# Sheet1.net
KiCad netlist of a schematic drawn in Altium Designer
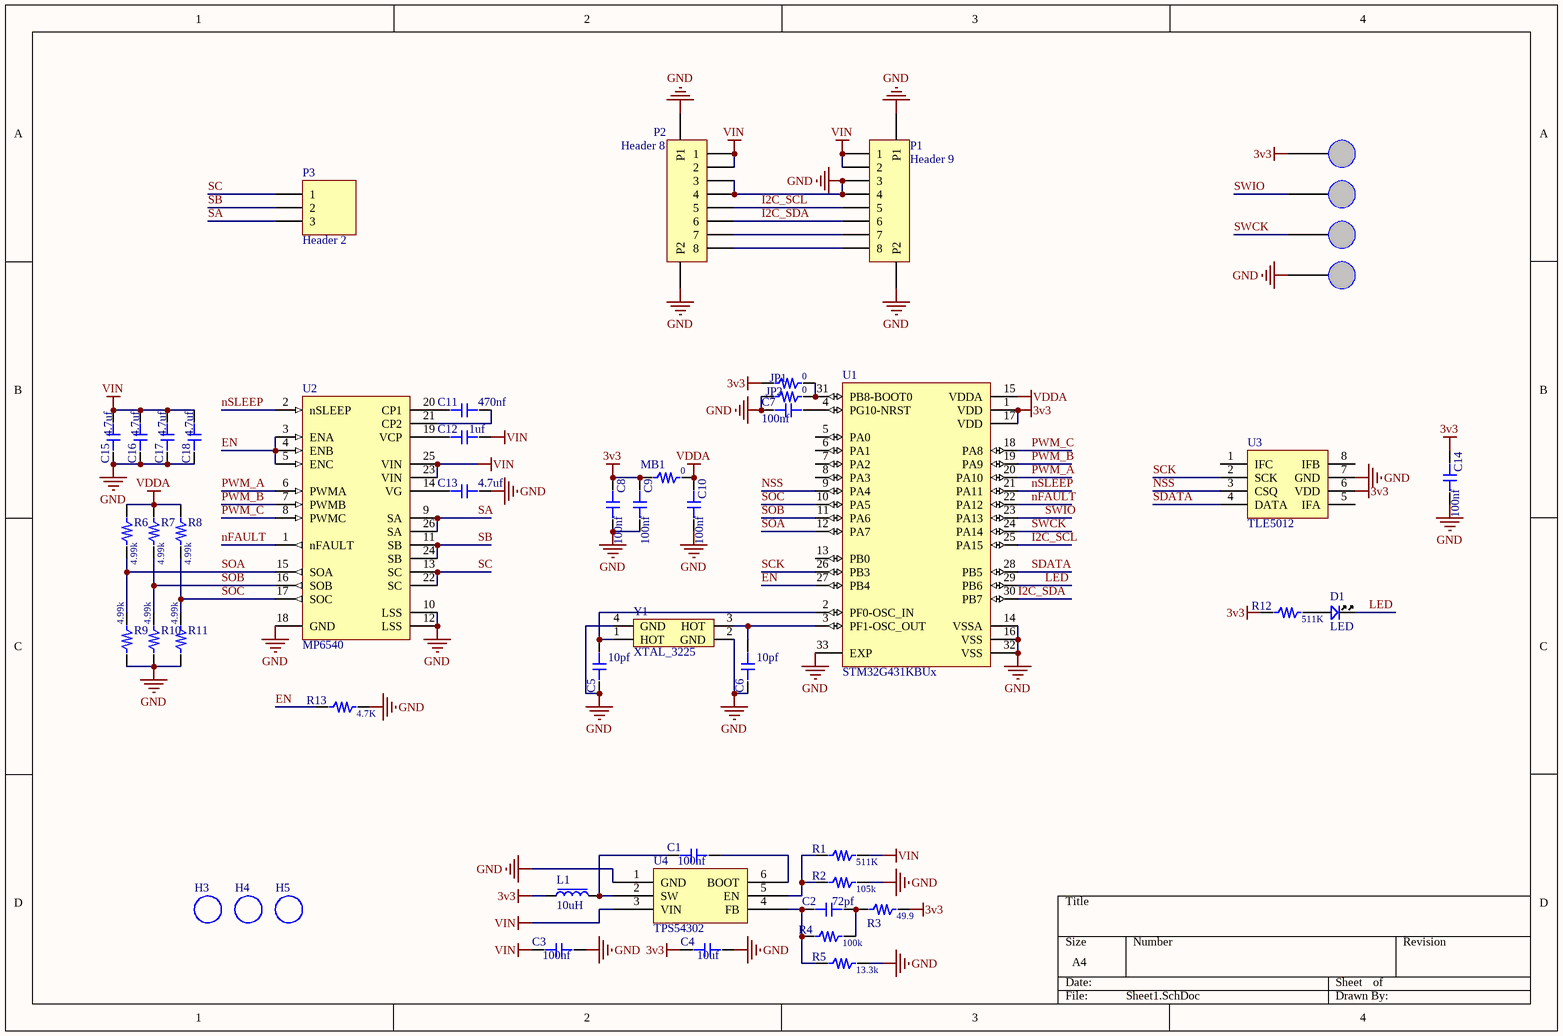
[diagram p0: Sheet1.SchDoc]

(export (version "E")
  (design (tool "Eeschema 10.0.6"))
  (components
    (comp (ref "3V3")
      (value "solder_pad")
      (footprint "solder_pad_1")
      (libsource (lib "zjti_lib") (part "solder_pad"))
    )
    (comp (ref "C1")
      (value "100nf")
      (footprint "C_0402")
      (fields (field (name "Comment") "C_0603"))
      (libsource (lib "zjti_lib") (part "C"))
    )
    (comp (ref "C2")
      (value "72pf")
      (footprint "C_0402")
      (fields (field (name "Comment") "C_0603"))
      (libsource (lib "zjti_lib") (part "C"))
    )
    (comp (ref "C3")
      (value "100nf")
      (footprint "C_0402")
      (fields (field (name "Comment") "C_0603"))
      (libsource (lib "zjti_lib") (part "C"))
    )
    (comp (ref "C4")
      (value "10uf")
      (footprint "C_0603")
      (fields (field (name "Comment") "C_0603"))
      (libsource (lib "zjti_lib") (part "C"))
    )
    (comp (ref "C5")
      (value "10pf")
      (footprint "C_0402")
      (fields (field (name "Comment") "C_0603"))
      (libsource (lib "zjti_lib") (part "C"))
    )
    (comp (ref "C6")
      (value "10pf")
      (footprint "C_0402")
      (fields (field (name "Comment") "C_0603"))
      (libsource (lib "zjti_lib") (part "C"))
    )
    (comp (ref "C7")
      (value "100nf")
      (footprint "C_0402")
      (fields (field (name "Comment") "C_0603"))
      (libsource (lib "zjti_lib") (part "C"))
    )
    (comp (ref "C8")
      (value "100nf")
      (footprint "C_0402")
      (fields (field (name "Comment") "C_0603"))
      (libsource (lib "zjti_lib") (part "C"))
    )
    (comp (ref "C9")
      (value "100nf")
      (footprint "C_0402")
      (fields (field (name "Comment") "C_0603"))
      (libsource (lib "zjti_lib") (part "C"))
    )
    (comp (ref "C10")
      (value "100nf")
      (footprint "C_0402")
      (fields (field (name "Comment") "C_0603"))
      (libsource (lib "zjti_lib") (part "C"))
    )
    (comp (ref "C11")
      (value "470nf")
      (footprint "C_0402")
      (fields (field (name "Comment") "C_0603"))
      (libsource (lib "zjti_lib") (part "C"))
    )
    (comp (ref "C12")
      (value "1uf")
      (footprint "C_0402")
      (fields (field (name "Comment") "C_0603"))
      (libsource (lib "zjti_lib") (part "C"))
    )
    (comp (ref "C13")
      (value "4.7uf")
      (footprint "C_0402")
      (fields (field (name "Comment") "C_0603"))
      (libsource (lib "zjti_lib") (part "C"))
    )
    (comp (ref "C14")
      (value "100nf")
      (footprint "C_0402")
      (fields (field (name "Comment") "C_0603"))
      (libsource (lib "zjti_lib") (part "C"))
    )
    (comp (ref "C15")
      (value "4.7uf")
      (footprint "C_0805")
      (fields (field (name "Comment") "C_0603"))
      (libsource (lib "zjti_lib") (part "C"))
    )
    (comp (ref "C16")
      (value "4.7uf")
      (footprint "C_0805")
      (fields (field (name "Comment") "C_0603"))
      (libsource (lib "zjti_lib") (part "C"))
    )
    (comp (ref "C17")
      (value "4.7uf")
      (footprint "C_0805")
      (fields (field (name "Comment") "C_0603"))
      (libsource (lib "zjti_lib") (part "C"))
    )
    (comp (ref "C18")
      (value "4.7uf")
      (footprint "C_0805")
      (fields (field (name "Comment") "C_0603"))
      (libsource (lib "zjti_lib") (part "C"))
    )
    (comp (ref "CK")
      (value "solder_pad")
      (footprint "solder_pad_1")
      (libsource (lib "zjti_lib") (part "solder_pad"))
    )
    (comp (ref "D1") (value "LED") (footprint "LED_0603") (libsource (lib "zjti_lib") (part "LED_SMD")))
    (comp (ref "GND")
      (value "solder_pad")
      (footprint "solder_pad_1")
      (libsource (lib "zjti_lib") (part "solder_pad"))
    )
    (comp (ref "H3")
      (value "~")
      (footprint "M3 Hole")
      (description "M3 Hole with no copper")
      (libsource (lib "CustomComponents") (part "M3 Hole"))
    )
    (comp (ref "H4")
      (value "~")
      (footprint "M3 Hole")
      (description "M3 Hole with no copper")
      (libsource (lib "CustomComponents") (part "M3 Hole"))
    )
    (comp (ref "H5")
      (value "~")
      (footprint "M3 Hole")
      (description "M3 Hole with no copper")
      (libsource (lib "CustomComponents") (part "M3 Hole"))
    )
    (comp (ref "IO")
      (value "solder_pad")
      (footprint "solder_pad_1")
      (libsource (lib "zjti_lib") (part "solder_pad"))
    )
    (comp (ref "JP1")
      (value "0")
      (footprint "R_0402")
      (fields (field (name "Comment") "R_0603"))
      (libsource (lib "zjti_lib") (part "R"))
    )
    (comp (ref "JP2")
      (value "0")
      (footprint "R_0402")
      (fields (field (name "Comment") "R_0603"))
      (libsource (lib "zjti_lib") (part "R"))
    )
    (comp (ref "L1")
      (value "10uH")
      (footprint "NR3015")
      (description "NR功率电感")
      (libsource (lib "zjti_lib") (part "L-NR"))
    )
    (comp (ref "MB1")
      (value "0")
      (footprint "R_0402")
      (fields (field (name "Comment") "R_0603"))
      (libsource (lib "zjti_lib") (part "R"))
    )
    (comp (ref "P1")
      (value "Header 9")
      (footprint "JST_SM08B-SRSS-TB(LF)(SN)")
      (description "Header, 5-Pin")
      (fields (field (name "PUBLISHER") "Altium Limited"))
      (libsource (lib "") (part "Header 8_1"))
    )
    (comp (ref "P2")
      (value "Header 8")
      (footprint "JST_SM08B-SRSS-TB(LF)(SN)")
      (description "Header, 5-Pin")
      (fields (field (name "PUBLISHER") "Altium Limited"))
      (libsource (lib "zjti_lib") (part "Header 8"))
    )
    (comp (ref "P3")
      (value "Header 2")
      (footprint "MOLEX_530480310")
      (description "Header, 2-Pin")
      (fields (field (name "PUBLISHER") "Altium Limited"))
      (libsource (lib "zjti_lib") (part "Header 3"))
    )
    (comp (ref "R1")
      (value "511K")
      (footprint "R_0402")
      (fields (field (name "Comment") "R_0603"))
      (libsource (lib "zjti_lib") (part "R"))
    )
    (comp (ref "R2")
      (value "105k")
      (footprint "R_0402")
      (fields (field (name "Comment") "R_0603"))
      (libsource (lib "zjti_lib") (part "R"))
    )
    (comp (ref "R3")
      (value "49.9")
      (footprint "R_0402")
      (fields (field (name "Comment") "R_0603"))
      (libsource (lib "zjti_lib") (part "R"))
    )
    (comp (ref "R4")
      (value "100k")
      (footprint "R_0402")
      (fields (field (name "Comment") "R_0603"))
      (libsource (lib "zjti_lib") (part "R"))
    )
    (comp (ref "R5")
      (value "13.3k")
      (footprint "R_0402")
      (fields (field (name "Comment") "R_0603"))
      (libsource (lib "zjti_lib") (part "R"))
    )
    (comp (ref "R6")
      (value "4.99k")
      (footprint "R_0402")
      (fields (field (name "Comment") "R_0603"))
      (libsource (lib "zjti_lib") (part "R"))
    )
    (comp (ref "R7")
      (value "4.99k")
      (footprint "R_0402")
      (fields (field (name "Comment") "R_0603"))
      (libsource (lib "zjti_lib") (part "R"))
    )
    (comp (ref "R8")
      (value "4.99k")
      (footprint "R_0402")
      (fields (field (name "Comment") "R_0603"))
      (libsource (lib "zjti_lib") (part "R"))
    )
    (comp (ref "R9")
      (value "4.99k")
      (footprint "R_0402")
      (fields (field (name "Comment") "R_0603"))
      (libsource (lib "zjti_lib") (part "R"))
    )
    (comp (ref "R10")
      (value "4.99k")
      (footprint "R_0402")
      (fields (field (name "Comment") "R_0603"))
      (libsource (lib "zjti_lib") (part "R"))
    )
    (comp (ref "R11")
      (value "4.99k")
      (footprint "R_0402")
      (fields (field (name "Comment") "R_0603"))
      (libsource (lib "zjti_lib") (part "R"))
    )
    (comp (ref "R12")
      (value "511K")
      (footprint "R_0402")
      (fields (field (name "Comment") "R_0603"))
      (libsource (lib "zjti_lib") (part "R"))
    )
    (comp (ref "R13")
      (value "4.7K")
      (footprint "R_0402")
      (fields (field (name "Comment") "R_0603"))
      (libsource (lib "zjti_lib") (part "R"))
    )
    (comp (ref "U1")
      (value "STM32G431KBUx")
      (footprint "QFN32")
      (description "ARMÂ® CortexÂ®-M4F STM32G4 Microcontroller IC 32-Bit 170MHz 128KB (128K x 8) FLASH 32-UFQFPN (5x5)")
      (fields (field (name "MP") "STM32G431KBU3") (field (name "MF") "STMicroelectronics"))
      (libsource (lib "zjti_lib") (part "STM32G431KBUx"))
    )
    (comp (ref "U2")
      (value "MP6540")
      (footprint "QFN26-MPS")
      (fields (field (name "MP") "STM32G431KBU3") (field (name "MF") "STMicroelectronics"))
      (libsource (lib "zjti_lib") (part "MP6540"))
    )
    (comp (ref "U3") (value "TLE5012") (footprint "SOIC8") (libsource (lib "zjti_lib") (part "TLE5012")))
    (comp (ref "U4") (value "TPS54302") (footprint "SOT-23-6") (libsource (lib "zjti_lib") (part "TPS54302")))
    (comp (ref "Y1")
      (value "XTAL_3225")
      (footprint "XTAL-2016")
      (libsource (lib "zjti_lib") (part "XTAL_3225"))
    )
  )
  (nets
    (net (code "1") (name "/EN") (class "Default")
      (node (ref "R13") (pin "1") (pinfunction "1_1") (pintype "passive"))
      (node (ref "U1") (pin "27") (pinfunction "PB4_27") (pintype "bidirectional"))
      (node (ref "U2") (pin "3") (pinfunction "ENA_3") (pintype "input"))
      (node (ref "U2") (pin "4") (pinfunction "ENB_4") (pintype "input"))
      (node (ref "U2") (pin "5") (pinfunction "ENC_5") (pintype "input"))
    )
    (net (code "2") (name "/I2C_SCL") (class "Default")
      (node (ref "P1") (pin "5") (pinfunction "5_5") (pintype "passive"))
      (node (ref "P2") (pin "5") (pinfunction "5_5") (pintype "passive"))
      (node (ref "U1") (pin "25") (pinfunction "PA15_25") (pintype "bidirectional"))
    )
    (net (code "3") (name "/I2C_SDA") (class "Default")
      (node (ref "P1") (pin "6") (pinfunction "6_6") (pintype "passive"))
      (node (ref "P2") (pin "6") (pinfunction "6_6") (pintype "passive"))
      (node (ref "U1") (pin "30") (pinfunction "PB7_30") (pintype "bidirectional"))
    )
    (net (code "4") (name "/LED") (class "Default")
      (node (ref "D1") (pin "C") (pintype "passive"))
      (node (ref "U1") (pin "29") (pinfunction "PB6_29") (pintype "bidirectional"))
    )
    (net (code "5") (name "/NSS") (class "Default")
      (node (ref "U1") (pin "9") (pinfunction "PA4_9") (pintype "bidirectional"))
      (node (ref "U3") (pin "3") (pinfunction "CSQ_3") (pintype "passive"))
    )
    (net (code "6") (name "/PWM_A") (class "Default")
      (node (ref "U1") (pin "20") (pinfunction "PA10_20") (pintype "bidirectional"))
      (node (ref "U2") (pin "6") (pinfunction "PWMA_6") (pintype "input"))
    )
    (net (code "7") (name "/PWM_B") (class "Default")
      (node (ref "U1") (pin "19") (pinfunction "PA9_19") (pintype "bidirectional"))
      (node (ref "U2") (pin "7") (pinfunction "PWMB_7") (pintype "input"))
    )
    (net (code "8") (name "/PWM_C") (class "Default")
      (node (ref "U1") (pin "18") (pinfunction "PA8_18") (pintype "bidirectional"))
      (node (ref "U2") (pin "8") (pinfunction "PWMC_8") (pintype "input"))
    )
    (net (code "9") (name "/SA") (class "Default")
      (node (ref "P3") (pin "3") (pinfunction "3_3") (pintype "passive"))
      (node (ref "U2") (pin "26") (pinfunction "SA_26") (pintype "power_in"))
      (node (ref "U2") (pin "9") (pinfunction "SA_9") (pintype "power_in"))
    )
    (net (code "10") (name "/SB") (class "Default")
      (node (ref "P3") (pin "2") (pinfunction "2_2") (pintype "passive"))
      (node (ref "U2") (pin "11") (pinfunction "SB_11") (pintype "power_in"))
      (node (ref "U2") (pin "24") (pinfunction "SB_24") (pintype "power_in"))
    )
    (net (code "11") (name "/SC") (class "Default")
      (node (ref "P3") (pin "1") (pinfunction "1_1") (pintype "passive"))
      (node (ref "U2") (pin "13") (pinfunction "SC_13") (pintype "power_in"))
      (node (ref "U2") (pin "22") (pinfunction "SC_22") (pintype "power_in"))
    )
    (net (code "12") (name "/SCK") (class "Default")
      (node (ref "U1") (pin "26") (pinfunction "PB3_26") (pintype "bidirectional"))
      (node (ref "U3") (pin "2") (pinfunction "SCK_2") (pintype "passive"))
    )
    (net (code "13") (name "/SDATA") (class "Default")
      (node (ref "U1") (pin "28") (pinfunction "PB5_28") (pintype "bidirectional"))
      (node (ref "U3") (pin "4") (pinfunction "DATA_4") (pintype "passive"))
    )
    (net (code "14") (name "/SOA") (class "Default")
      (node (ref "R6") (pin "1") (pinfunction "1_1") (pintype "passive"))
      (node (ref "R9") (pin "2") (pinfunction "2_2") (pintype "passive"))
      (node (ref "U1") (pin "12") (pinfunction "PA7_12") (pintype "bidirectional"))
      (node (ref "U2") (pin "15") (pinfunction "SOA_15") (pintype "output"))
    )
    (net (code "15") (name "/SOB") (class "Default")
      (node (ref "R10") (pin "2") (pinfunction "2_2") (pintype "passive"))
      (node (ref "R7") (pin "1") (pinfunction "1_1") (pintype "passive"))
      (node (ref "U1") (pin "11") (pinfunction "PA6_11") (pintype "bidirectional"))
      (node (ref "U2") (pin "16") (pinfunction "SOB_16") (pintype "output"))
    )
    (net (code "16") (name "/SOC") (class "Default")
      (node (ref "R11") (pin "2") (pinfunction "2_2") (pintype "passive"))
      (node (ref "R8") (pin "1") (pinfunction "1_1") (pintype "passive"))
      (node (ref "U1") (pin "10") (pinfunction "PA5_10") (pintype "bidirectional"))
      (node (ref "U2") (pin "17") (pinfunction "SOC_17") (pintype "output"))
    )
    (net (code "17") (name "/SWCK") (class "Default")
      (node (ref "CK") (pin "1") (pinfunction "1_1") (pintype "passive"))
      (node (ref "U1") (pin "24") (pinfunction "PA14_24") (pintype "bidirectional"))
    )
    (net (code "18") (name "/SWIO") (class "Default")
      (node (ref "IO") (pin "1") (pinfunction "1_1") (pintype "passive"))
      (node (ref "U1") (pin "23") (pinfunction "PA13_23") (pintype "bidirectional"))
    )
    (net (code "19") (name "/nFAULT") (class "Default")
      (node (ref "U1") (pin "22") (pinfunction "PA12_22") (pintype "bidirectional"))
      (node (ref "U2") (pin "1") (pinfunction "nFAULT_1") (pintype "output"))
    )
    (net (code "20") (name "/nSLEEP") (class "Default")
      (node (ref "U1") (pin "21") (pinfunction "PA11_21") (pintype "bidirectional"))
      (node (ref "U2") (pin "2") (pinfunction "nSLEEP_2") (pintype "input"))
    )
    (net (code "21") (name "3v3") (class "Default")
      (node (ref "3V3") (pin "1") (pinfunction "1_1") (pintype "passive"))
      (node (ref "C14") (pin "1") (pinfunction "1_1") (pintype "passive"))
      (node (ref "C4") (pin "1") (pinfunction "1_1") (pintype "passive"))
      (node (ref "C8") (pin "1") (pinfunction "1_1") (pintype "passive"))
      (node (ref "C9") (pin "1") (pinfunction "1_1") (pintype "passive"))
      (node (ref "JP1") (pin "1") (pinfunction "1_1") (pintype "passive"))
      (node (ref "L1") (pin "1") (pinfunction "1_1") (pintype "passive"))
      (node (ref "MB1") (pin "1") (pinfunction "1_1") (pintype "passive"))
      (node (ref "R12") (pin "1") (pinfunction "1_1") (pintype "passive"))
      (node (ref "R3") (pin "2") (pinfunction "2_2") (pintype "passive"))
      (node (ref "U1") (pin "1") (pinfunction "VDD_1") (pintype "power_in"))
      (node (ref "U1") (pin "17") (pinfunction "VDD_17") (pintype "power_in"))
      (node (ref "U3") (pin "6") (pinfunction "VDD_6") (pintype "passive"))
    )
    (net (code "22") (name "GND") (class "Default")
      (node (ref "C10") (pin "2") (pinfunction "2_2") (pintype "passive"))
      (node (ref "C13") (pin "2") (pinfunction "2_2") (pintype "passive"))
      (node (ref "C14") (pin "2") (pinfunction "2_2") (pintype "passive"))
      (node (ref "C15") (pin "1") (pinfunction "1_1") (pintype "passive"))
      (node (ref "C16") (pin "1") (pinfunction "1_1") (pintype "passive"))
      (node (ref "C17") (pin "1") (pinfunction "1_1") (pintype "passive"))
      (node (ref "C18") (pin "1") (pinfunction "1_1") (pintype "passive"))
      (node (ref "C3") (pin "2") (pinfunction "2_2") (pintype "passive"))
      (node (ref "C4") (pin "2") (pinfunction "2_2") (pintype "passive"))
      (node (ref "C5") (pin "1") (pinfunction "1_1") (pintype "passive"))
      (node (ref "C6") (pin "1") (pinfunction "1_1") (pintype "passive"))
      (node (ref "C7") (pin "1") (pinfunction "1_1") (pintype "passive"))
      (node (ref "C8") (pin "2") (pinfunction "2_2") (pintype "passive"))
      (node (ref "C9") (pin "2") (pinfunction "2_2") (pintype "passive"))
      (node (ref "GND") (pin "1") (pinfunction "1_1") (pintype "passive"))
      (node (ref "JP2") (pin "1") (pinfunction "1_1") (pintype "passive"))
      (node (ref "P1") (pin "3") (pinfunction "3_3") (pintype "passive"))
      (node (ref "P1") (pin "4") (pinfunction "4_4") (pintype "passive"))
      (node (ref "P1") (pin "P1") (pinfunction "P1_P1") (pintype "passive"))
      (node (ref "P1") (pin "P2") (pinfunction "P2_P2") (pintype "passive"))
      (node (ref "P2") (pin "3") (pinfunction "3_3") (pintype "passive"))
      (node (ref "P2") (pin "4") (pinfunction "4_4") (pintype "passive"))
      (node (ref "P2") (pin "P1") (pinfunction "P1_P1") (pintype "passive"))
      (node (ref "P2") (pin "P2") (pinfunction "P2_P2") (pintype "passive"))
      (node (ref "R10") (pin "1") (pinfunction "1_1") (pintype "passive"))
      (node (ref "R11") (pin "1") (pinfunction "1_1") (pintype "passive"))
      (node (ref "R13") (pin "2") (pinfunction "2_2") (pintype "passive"))
      (node (ref "R2") (pin "2") (pinfunction "2_2") (pintype "passive"))
      (node (ref "R5") (pin "2") (pinfunction "2_2") (pintype "passive"))
      (node (ref "R9") (pin "1") (pinfunction "1_1") (pintype "passive"))
      (node (ref "U1") (pin "14") (pinfunction "VSSA_14") (pintype "power_in"))
      (node (ref "U1") (pin "16") (pinfunction "VSS_16") (pintype "power_in"))
      (node (ref "U1") (pin "32") (pinfunction "VSS_32") (pintype "power_in"))
      (node (ref "U1") (pin "33") (pinfunction "EXP_33") (pintype "power_in"))
      (node (ref "U2") (pin "10") (pinfunction "LSS_10") (pintype "power_in"))
      (node (ref "U2") (pin "12") (pinfunction "LSS_12") (pintype "power_in"))
      (node (ref "U2") (pin "18") (pinfunction "GND_18") (pintype "power_in"))
      (node (ref "U3") (pin "7") (pinfunction "GND_7") (pintype "passive"))
      (node (ref "U4") (pin "1") (pinfunction "GND_1") (pintype "passive"))
      (node (ref "Y1") (pin "2") (pinfunction "GND_2") (pintype "passive"))
      (node (ref "Y1") (pin "4") (pinfunction "GND_4") (pintype "passive"))
    )
    (net (code "23") (name "Net-(C2-Pad2)") (class "Default")
      (node (ref "C2") (pin "2") (pinfunction "2_2") (pintype "passive"))
      (node (ref "R3") (pin "1") (pinfunction "1_1") (pintype "passive"))
      (node (ref "R4") (pin "2") (pinfunction "2_2") (pintype "passive"))
    )
    (net (code "24") (name "Net-(D1-PadA)") (class "Default")
      (node (ref "D1") (pin "A") (pintype "passive"))
      (node (ref "R12") (pin "2") (pinfunction "2_2") (pintype "passive"))
    )
    (net (code "25") (name "Net-(P1-Pad7)") (class "Default")
      (node (ref "P1") (pin "7") (pinfunction "7_7") (pintype "passive"))
      (node (ref "P2") (pin "7") (pinfunction "7_7") (pintype "passive"))
    )
    (net (code "26") (name "Net-(P1-Pad8)") (class "Default")
      (node (ref "P1") (pin "8") (pinfunction "8_8") (pintype "passive"))
      (node (ref "P2") (pin "8") (pinfunction "8_8") (pintype "passive"))
    )
    (net (code "27") (name "Net-(U1-PB8-BOOT0)") (class "Default")
      (node (ref "JP1") (pin "2") (pinfunction "2_2") (pintype "passive"))
      (node (ref "JP2") (pin "2") (pinfunction "2_2") (pintype "passive"))
      (node (ref "U1") (pin "31") (pinfunction "PB8-BOOT0_31") (pintype "bidirectional"))
    )
    (net (code "28") (name "Net-(U1-PF0-OSC_IN)") (class "Default")
      (node (ref "C5") (pin "2") (pinfunction "2_2") (pintype "passive"))
      (node (ref "U1") (pin "2") (pinfunction "PF0-OSC_IN_2") (pintype "bidirectional"))
      (node (ref "Y1") (pin "1") (pinfunction "HOT_1") (pintype "passive"))
    )
    (net (code "29") (name "Net-(U1-PF1-OSC_OUT)") (class "Default")
      (node (ref "C6") (pin "2") (pinfunction "2_2") (pintype "passive"))
      (node (ref "U1") (pin "3") (pinfunction "PF1-OSC_OUT_3") (pintype "bidirectional"))
      (node (ref "Y1") (pin "3") (pinfunction "HOT_3") (pintype "passive"))
    )
    (net (code "30") (name "Net-(U1-PG10-NRST)") (class "Default")
      (node (ref "C7") (pin "2") (pinfunction "2_2") (pintype "passive"))
      (node (ref "U1") (pin "4") (pinfunction "PG10-NRST_4") (pintype "bidirectional"))
    )
    (net (code "31") (name "Net-(U2-CP1)") (class "Default")
      (node (ref "C11") (pin "1") (pinfunction "1_1") (pintype "passive"))
      (node (ref "U2") (pin "20") (pinfunction "CP1_20") (pintype "passive"))
    )
    (net (code "32") (name "Net-(U2-CP2)") (class "Default")
      (node (ref "C11") (pin "2") (pinfunction "2_2") (pintype "passive"))
      (node (ref "U2") (pin "21") (pinfunction "CP2_21") (pintype "passive"))
    )
    (net (code "33") (name "Net-(U2-VCP)") (class "Default")
      (node (ref "C12") (pin "1") (pinfunction "1_1") (pintype "passive"))
      (node (ref "U2") (pin "19") (pinfunction "VCP_19") (pintype "power_in"))
    )
    (net (code "34") (name "Net-(U2-VG)") (class "Default")
      (node (ref "C13") (pin "1") (pinfunction "1_1") (pintype "passive"))
      (node (ref "U2") (pin "14") (pinfunction "VG_14") (pintype "power_in"))
    )
    (net (code "35") (name "Net-(U4-BOOT)") (class "Default")
      (node (ref "C1") (pin "2") (pinfunction "2_2") (pintype "passive"))
      (node (ref "U4") (pin "6") (pinfunction "BOOT_6") (pintype "passive"))
    )
    (net (code "36") (name "Net-(U4-EN)") (class "Default")
      (node (ref "R1") (pin "1") (pinfunction "1_1") (pintype "passive"))
      (node (ref "R2") (pin "1") (pinfunction "1_1") (pintype "passive"))
      (node (ref "U4") (pin "5") (pinfunction "EN_5") (pintype "passive"))
    )
    (net (code "37") (name "Net-(U4-FB)") (class "Default")
      (node (ref "C2") (pin "1") (pinfunction "1_1") (pintype "passive"))
      (node (ref "R4") (pin "1") (pinfunction "1_1") (pintype "passive"))
      (node (ref "R5") (pin "1") (pinfunction "1_1") (pintype "passive"))
      (node (ref "U4") (pin "4") (pinfunction "FB_4") (pintype "passive"))
    )
    (net (code "38") (name "Net-(U4-SW)") (class "Default")
      (node (ref "C1") (pin "1") (pinfunction "1_1") (pintype "passive"))
      (node (ref "L1") (pin "2") (pinfunction "2_2") (pintype "passive"))
      (node (ref "U4") (pin "2") (pinfunction "SW_2") (pintype "passive"))
    )
    (net (code "39") (name "VDDA") (class "Default")
      (node (ref "C10") (pin "1") (pinfunction "1_1") (pintype "passive"))
      (node (ref "MB1") (pin "2") (pinfunction "2_2") (pintype "passive"))
      (node (ref "R6") (pin "2") (pinfunction "2_2") (pintype "passive"))
      (node (ref "R7") (pin "2") (pinfunction "2_2") (pintype "passive"))
      (node (ref "R8") (pin "2") (pinfunction "2_2") (pintype "passive"))
      (node (ref "U1") (pin "15") (pinfunction "VDDA_15") (pintype "power_in"))
    )
    (net (code "40") (name "VIN") (class "Default")
      (node (ref "C12") (pin "2") (pinfunction "2_2") (pintype "passive"))
      (node (ref "C15") (pin "2") (pinfunction "2_2") (pintype "passive"))
      (node (ref "C16") (pin "2") (pinfunction "2_2") (pintype "passive"))
      (node (ref "C17") (pin "2") (pinfunction "2_2") (pintype "passive"))
      (node (ref "C18") (pin "2") (pinfunction "2_2") (pintype "passive"))
      (node (ref "C3") (pin "1") (pinfunction "1_1") (pintype "passive"))
      (node (ref "P1") (pin "1") (pinfunction "1_1") (pintype "passive"))
      (node (ref "P1") (pin "2") (pinfunction "2_2") (pintype "passive"))
      (node (ref "P2") (pin "1") (pinfunction "1_1") (pintype "passive"))
      (node (ref "P2") (pin "2") (pinfunction "2_2") (pintype "passive"))
      (node (ref "R1") (pin "2") (pinfunction "2_2") (pintype "passive"))
      (node (ref "U2") (pin "23") (pinfunction "VIN_23") (pintype "power_in"))
      (node (ref "U2") (pin "25") (pinfunction "VIN_25") (pintype "power_in"))
      (node (ref "U4") (pin "3") (pinfunction "VIN_3") (pintype "passive"))
    )
    (net (code "41") (name "unconnected-(U1-PA0-Pad5)") (class "Default")
      (node (ref "U1") (pin "5") (pinfunction "PA0_5") (pintype "bidirectional"))
    )
    (net (code "42") (name "unconnected-(U1-PA1-Pad6)") (class "Default")
      (node (ref "U1") (pin "6") (pinfunction "PA1_6") (pintype "bidirectional"))
    )
    (net (code "43") (name "unconnected-(U1-PA2-Pad7)") (class "Default")
      (node (ref "U1") (pin "7") (pinfunction "PA2_7") (pintype "bidirectional"))
    )
    (net (code "44") (name "unconnected-(U1-PA3-Pad8)") (class "Default")
      (node (ref "U1") (pin "8") (pinfunction "PA3_8") (pintype "bidirectional"))
    )
    (net (code "45") (name "unconnected-(U1-PB0-Pad13)") (class "Default")
      (node (ref "U1") (pin "13") (pinfunction "PB0_13") (pintype "bidirectional"))
    )
    (net (code "46") (name "unconnected-(U3-IFA-Pad5)") (class "Default")
      (node (ref "U3") (pin "5") (pinfunction "IFA_5") (pintype "passive"))
    )
    (net (code "47") (name "unconnected-(U3-IFB-Pad8)") (class "Default")
      (node (ref "U3") (pin "8") (pinfunction "IFB_8") (pintype "passive"))
    )
    (net (code "48") (name "unconnected-(U3-IFC-Pad1)") (class "Default")
      (node (ref "U3") (pin "1") (pinfunction "IFC_1") (pintype "passive"))
    )
  )
)
